# Schematics.net
KiCad netlist of a schematic drawn in Altium Designer
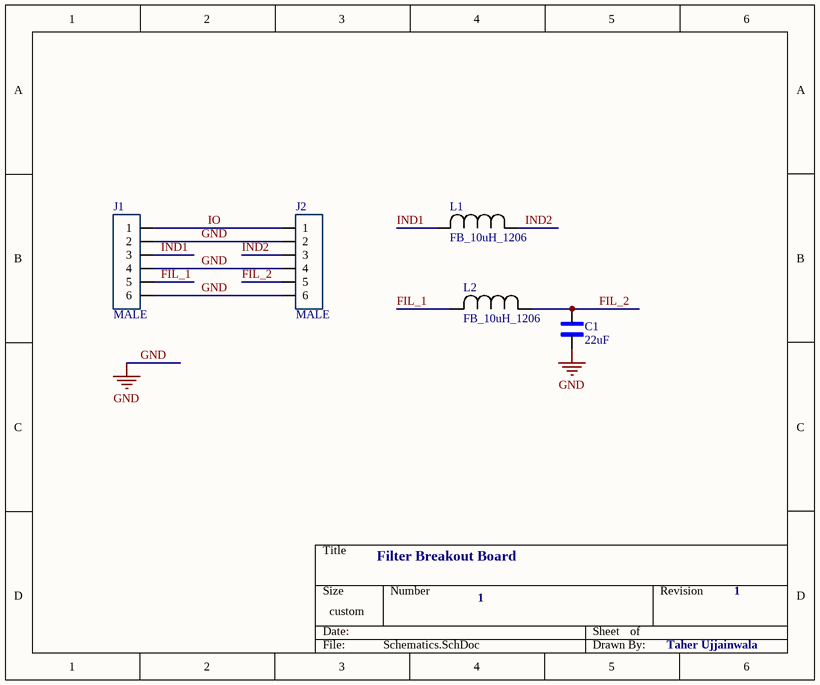
[diagram p0: Schematics.SchDoc]

(export (version "E")
  (design (tool "Eeschema 10.0.6"))
  (components
    (comp (ref "C1")
      (value "22uF")
      (footprint "1206_Passive_Capacitor")
      (description "22uF ±10% 25V X5R 1206 Multilayer Ceramic Capacitors MLCC - SMD/SMT RoHS")
      (fields (field (name "MFR PART #") "CL31A226KAHNNNE") (field (name "LCSC PART#") "C12891"))
      (libsource (lib "ECEN5730Lib_2023_01_DS") (part "C_22uF_1206"))
    )
    (comp (ref "J1")
      (value "MALE")
      (footprint "6_PIN_100MIL-Male")
      (description "Male header- 6 pin 1 row- through Hole")
      (fields (field (name "LCSC PART#") "C37208"))
      (libsource (lib "") (part "JM_6_PIN_MALE_1"))
    )
    (comp (ref "J2")
      (value "MALE")
      (footprint "6_PIN_100MIL-Male")
      (description "Male header- 6 pin 1 row- through Hole")
      (fields (field (name "LCSC PART#") "C37208"))
      (libsource (lib "ECEN5730Lib_2023_01_DS") (part "JM_6_PIN_MALE"))
    )
    (comp (ref "L1")
      (value "FB_10uH_1206")
      (footprint "AIML-1206_ABR-M")
      (description "25mA 10uH ±10% 800mΩ 1206  Inductors (SMD) ROHS")
      (fields (field (name "MFR PART #") "CMI321609X100KT") (field (name "LCSC PART#") "C1051"))
      (libsource (lib "ECEN5730Lib_2023_01_DS") (part "FB_10uH_1206"))
    )
    (comp (ref "L2")
      (value "FB_10uH_1206")
      (footprint "AIML-1206_ABR-M")
      (description "25mA 10uH ±10% 800mΩ 1206  Inductors (SMD) ROHS")
      (fields (field (name "MFR PART #") "CMI321609X100KT") (field (name "LCSC PART#") "C1051"))
      (libsource (lib "ECEN5730Lib_2023_01_DS") (part "FB_10uH_1206"))
    )
  )
  (nets
    (net (code "1") (name "/FIL_1") (class "Default")
      (node (ref "J1") (pin "5") (pinfunction "5_5") (pintype "passive"))
      (node (ref "L2") (pin "2") (pinfunction "2_2") (pintype "passive"))
    )
    (net (code "2") (name "/FIL_2") (class "Default")
      (node (ref "C1") (pin "2") (pinfunction "2_2") (pintype "passive"))
      (node (ref "J2") (pin "5") (pinfunction "5_5") (pintype "passive"))
      (node (ref "L2") (pin "1") (pinfunction "1_1") (pintype "passive"))
    )
    (net (code "3") (name "/IND1") (class "Default")
      (node (ref "J1") (pin "3") (pinfunction "3_3") (pintype "passive"))
      (node (ref "L1") (pin "2") (pinfunction "2_2") (pintype "passive"))
    )
    (net (code "4") (name "/IND2") (class "Default")
      (node (ref "J2") (pin "3") (pinfunction "3_3") (pintype "passive"))
      (node (ref "L1") (pin "1") (pinfunction "1_1") (pintype "passive"))
    )
    (net (code "5") (name "/IO") (class "Default")
      (node (ref "J1") (pin "1") (pinfunction "1_1") (pintype "passive"))
      (node (ref "J2") (pin "1") (pinfunction "1_1") (pintype "passive"))
    )
    (net (code "6") (name "GND") (class "Default")
      (node (ref "C1") (pin "1") (pinfunction "1_1") (pintype "passive"))
      (node (ref "J1") (pin "2") (pinfunction "2_2") (pintype "passive"))
      (node (ref "J1") (pin "4") (pinfunction "4_4") (pintype "passive"))
      (node (ref "J1") (pin "6") (pinfunction "6_6") (pintype "passive"))
      (node (ref "J2") (pin "2") (pinfunction "2_2") (pintype "passive"))
      (node (ref "J2") (pin "4") (pinfunction "4_4") (pintype "passive"))
      (node (ref "J2") (pin "6") (pinfunction "6_6") (pintype "passive"))
    )
  )
)
